# servo_pwr.net
KiCad netlist of a schematic drawn in Altium Designer
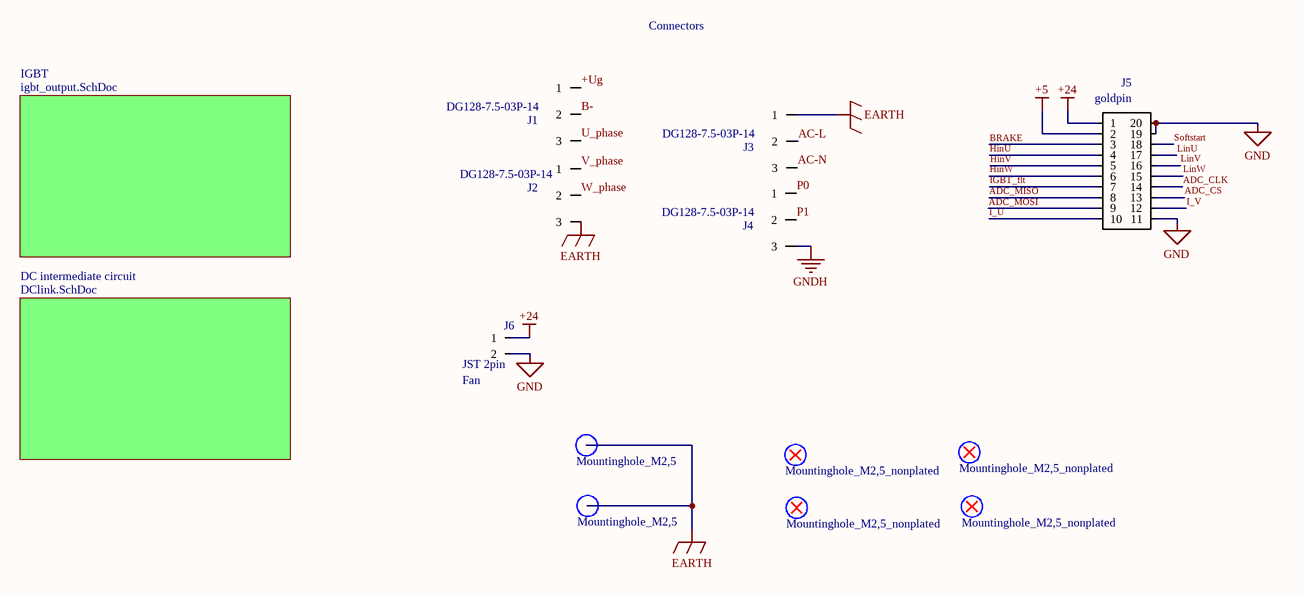
[diagram p0: servo_pwr.SchDoc]

(export (version "E")
  (design (tool "Eeschema 10.0.6"))
  (components
    (comp (ref "J1")
      (value "DG128-7.5-03P-14")
      (footprint "DG128-7.5-03P-14")
      (libsource (lib "connector") (part "DG128-7.5-03P-14"))
    )
    (comp (ref "J2")
      (value "DG128-7.5-03P-14")
      (footprint "DG128-7.5-03P-14")
      (libsource (lib "connector") (part "DG128-7.5-03P-14"))
    )
    (comp (ref "J3")
      (value "DG128-7.5-03P-14")
      (footprint "DG128-7.5-03P-14")
      (libsource (lib "connector") (part "DG128-7.5-03P-14"))
    )
    (comp (ref "J4")
      (value "DG128-7.5-03P-14")
      (footprint "DG128-7.5-03P-14")
      (libsource (lib "connector") (part "DG128-7.5-03P-14"))
    )
    (comp (ref "J5")
      (value "goldpin")
      (footprint "goldpin 2x10")
      (libsource (lib "connector") (part "goldpin"))
    )
    (comp (ref "J6")
      (value "JST 2pin")
      (footprint "JST XH 2pin")
      (libsource (lib "jst 2pin") (part "JST 2pin"))
    )
    (comp (ref "MH3")
      (value "Mountinghole_M2,5")
      (footprint "Mountinghole M2,5")
      (libsource (lib "mountinghole") (part "Mountinghole_M2,5"))
    )
    (comp (ref "MH4")
      (value "Mountinghole_M2,5")
      (footprint "Mountinghole M2,5")
      (libsource (lib "mountinghole") (part "Mountinghole_M2,5"))
    )
    (comp (ref "MH5")
      (value "Mountinghole_M2,5_nonplated")
      (footprint "Mountinghole M2,5 non plated")
      (libsource (lib "mountinghole") (part "Mountinghole_M2,5_nonplated"))
    )
    (comp (ref "MH6")
      (value "Mountinghole_M2,5_nonplated")
      (footprint "Mountinghole M2,5 non plated")
      (libsource (lib "mountinghole") (part "Mountinghole_M2,5_nonplated"))
    )
    (comp (ref "MH7")
      (value "Mountinghole_M2,5_nonplated")
      (footprint "Mountinghole M2,5 non plated")
      (libsource (lib "mountinghole") (part "Mountinghole_M2,5_nonplated"))
    )
    (comp (ref "MH8")
      (value "Mountinghole_M2,5_nonplated")
      (footprint "Mountinghole M2,5 non plated")
      (libsource (lib "mountinghole") (part "Mountinghole_M2,5_nonplated"))
    )
  )
  (nets
    (net (code "1") (name "+5") (class "Default")
      (node (ref "J5") (pin "2") (pinfunction "2_2") (pintype "passive"))
    )
    (net (code "2") (name "+24") (class "Default")
      (node (ref "J5") (pin "1") (pinfunction "1_1") (pintype "passive"))
      (node (ref "J6") (pin "1") (pinfunction "1_1") (pintype "passive"))
    )
    (net (code "3") (name "/+Ug") (class "Default")
      (node (ref "J1") (pin "1") (pinfunction "1_1") (pintype "passive"))
    )
    (net (code "4") (name "/AC-L") (class "Default")
      (node (ref "J3") (pin "2") (pinfunction "2_2") (pintype "passive"))
    )
    (net (code "5") (name "/AC-N") (class "Default")
      (node (ref "J3") (pin "3") (pinfunction "3_3") (pintype "passive"))
    )
    (net (code "6") (name "/ADC_CLK") (class "Default")
      (node (ref "J5") (pin "14") (pinfunction "14_14") (pintype "passive"))
    )
    (net (code "7") (name "/ADC_CS") (class "Default")
      (node (ref "J5") (pin "13") (pinfunction "13_13") (pintype "passive"))
    )
    (net (code "8") (name "/ADC_MISO") (class "Default")
      (node (ref "J5") (pin "8") (pinfunction "8_8") (pintype "passive"))
    )
    (net (code "9") (name "/ADC_MOSI") (class "Default")
      (node (ref "J5") (pin "9") (pinfunction "9_9") (pintype "passive"))
    )
    (net (code "10") (name "/B-") (class "Default")
      (node (ref "J1") (pin "2") (pinfunction "2_2") (pintype "passive"))
    )
    (net (code "11") (name "/BRAKE") (class "Default")
      (node (ref "J5") (pin "3") (pinfunction "3_3") (pintype "passive"))
    )
    (net (code "12") (name "/HinU") (class "Default")
      (node (ref "J5") (pin "4") (pinfunction "4_4") (pintype "passive"))
    )
    (net (code "13") (name "/HinV") (class "Default")
      (node (ref "J5") (pin "5") (pinfunction "5_5") (pintype "passive"))
    )
    (net (code "14") (name "/HinW") (class "Default")
      (node (ref "J5") (pin "6") (pinfunction "6_6") (pintype "passive"))
    )
    (net (code "15") (name "/IGBT_flt") (class "Default")
      (node (ref "J5") (pin "7") (pinfunction "7_7") (pintype "passive"))
    )
    (net (code "16") (name "/I_U") (class "Default")
      (node (ref "J5") (pin "10") (pinfunction "10_10") (pintype "passive"))
    )
    (net (code "17") (name "/I_V") (class "Default")
      (node (ref "J5") (pin "12") (pinfunction "12_12") (pintype "passive"))
    )
    (net (code "18") (name "/LinU") (class "Default")
      (node (ref "J5") (pin "17") (pinfunction "17_17") (pintype "passive"))
    )
    (net (code "19") (name "/LinV") (class "Default")
      (node (ref "J5") (pin "16") (pinfunction "16_16") (pintype "passive"))
    )
    (net (code "20") (name "/LinW") (class "Default")
      (node (ref "J5") (pin "15") (pinfunction "15_15") (pintype "passive"))
    )
    (net (code "21") (name "/P0") (class "Default")
      (node (ref "J4") (pin "1") (pinfunction "1_1") (pintype "passive"))
    )
    (net (code "22") (name "/P1") (class "Default")
      (node (ref "J4") (pin "2") (pinfunction "2_2") (pintype "passive"))
    )
    (net (code "23") (name "/Softstart") (class "Default")
      (node (ref "J5") (pin "18") (pinfunction "18_18") (pintype "passive"))
    )
    (net (code "24") (name "/U_phase") (class "Default")
      (node (ref "J1") (pin "3") (pinfunction "3_3") (pintype "passive"))
    )
    (net (code "25") (name "/V_phase") (class "Default")
      (node (ref "J2") (pin "1") (pinfunction "1_1") (pintype "passive"))
    )
    (net (code "26") (name "/W_phase") (class "Default")
      (node (ref "J2") (pin "2") (pinfunction "2_2") (pintype "passive"))
    )
    (net (code "27") (name "EARTH") (class "Default")
      (node (ref "J2") (pin "3") (pinfunction "3_3") (pintype "passive"))
      (node (ref "J3") (pin "1") (pinfunction "1_1") (pintype "passive"))
      (node (ref "MH3") (pin "1") (pinfunction "1_1") (pintype "passive"))
      (node (ref "MH4") (pin "1") (pinfunction "1_1") (pintype "passive"))
    )
    (net (code "28") (name "GND") (class "Default")
      (node (ref "J5") (pin "11") (pinfunction "11_11") (pintype "passive"))
      (node (ref "J5") (pin "19") (pinfunction "19_19") (pintype "passive"))
      (node (ref "J5") (pin "20") (pinfunction "20_20") (pintype "passive"))
      (node (ref "J6") (pin "2") (pinfunction "2_2") (pintype "passive"))
    )
    (net (code "29") (name "GNDH") (class "Default")
      (node (ref "J4") (pin "3") (pinfunction "3_3") (pintype "passive"))
    )
    (net (code "30") (name "unconnected-(MH5-Pad1)") (class "Default")
      (node (ref "MH5") (pin "1") (pinfunction "1_1") (pintype "passive+no_connect"))
    )
    (net (code "31") (name "unconnected-(MH6-Pad1)") (class "Default")
      (node (ref "MH6") (pin "1") (pinfunction "1_1") (pintype "passive+no_connect"))
    )
    (net (code "32") (name "unconnected-(MH7-Pad1)") (class "Default")
      (node (ref "MH7") (pin "1") (pinfunction "1_1") (pintype "passive+no_connect"))
    )
    (net (code "33") (name "unconnected-(MH8-Pad1)") (class "Default")
      (node (ref "MH8") (pin "1") (pinfunction "1_1") (pintype "passive+no_connect"))
    )
  )
)
